# Adafruit_NeoKey_Breakout.net
KiCad netlist of a schematic drawn in EAGLE
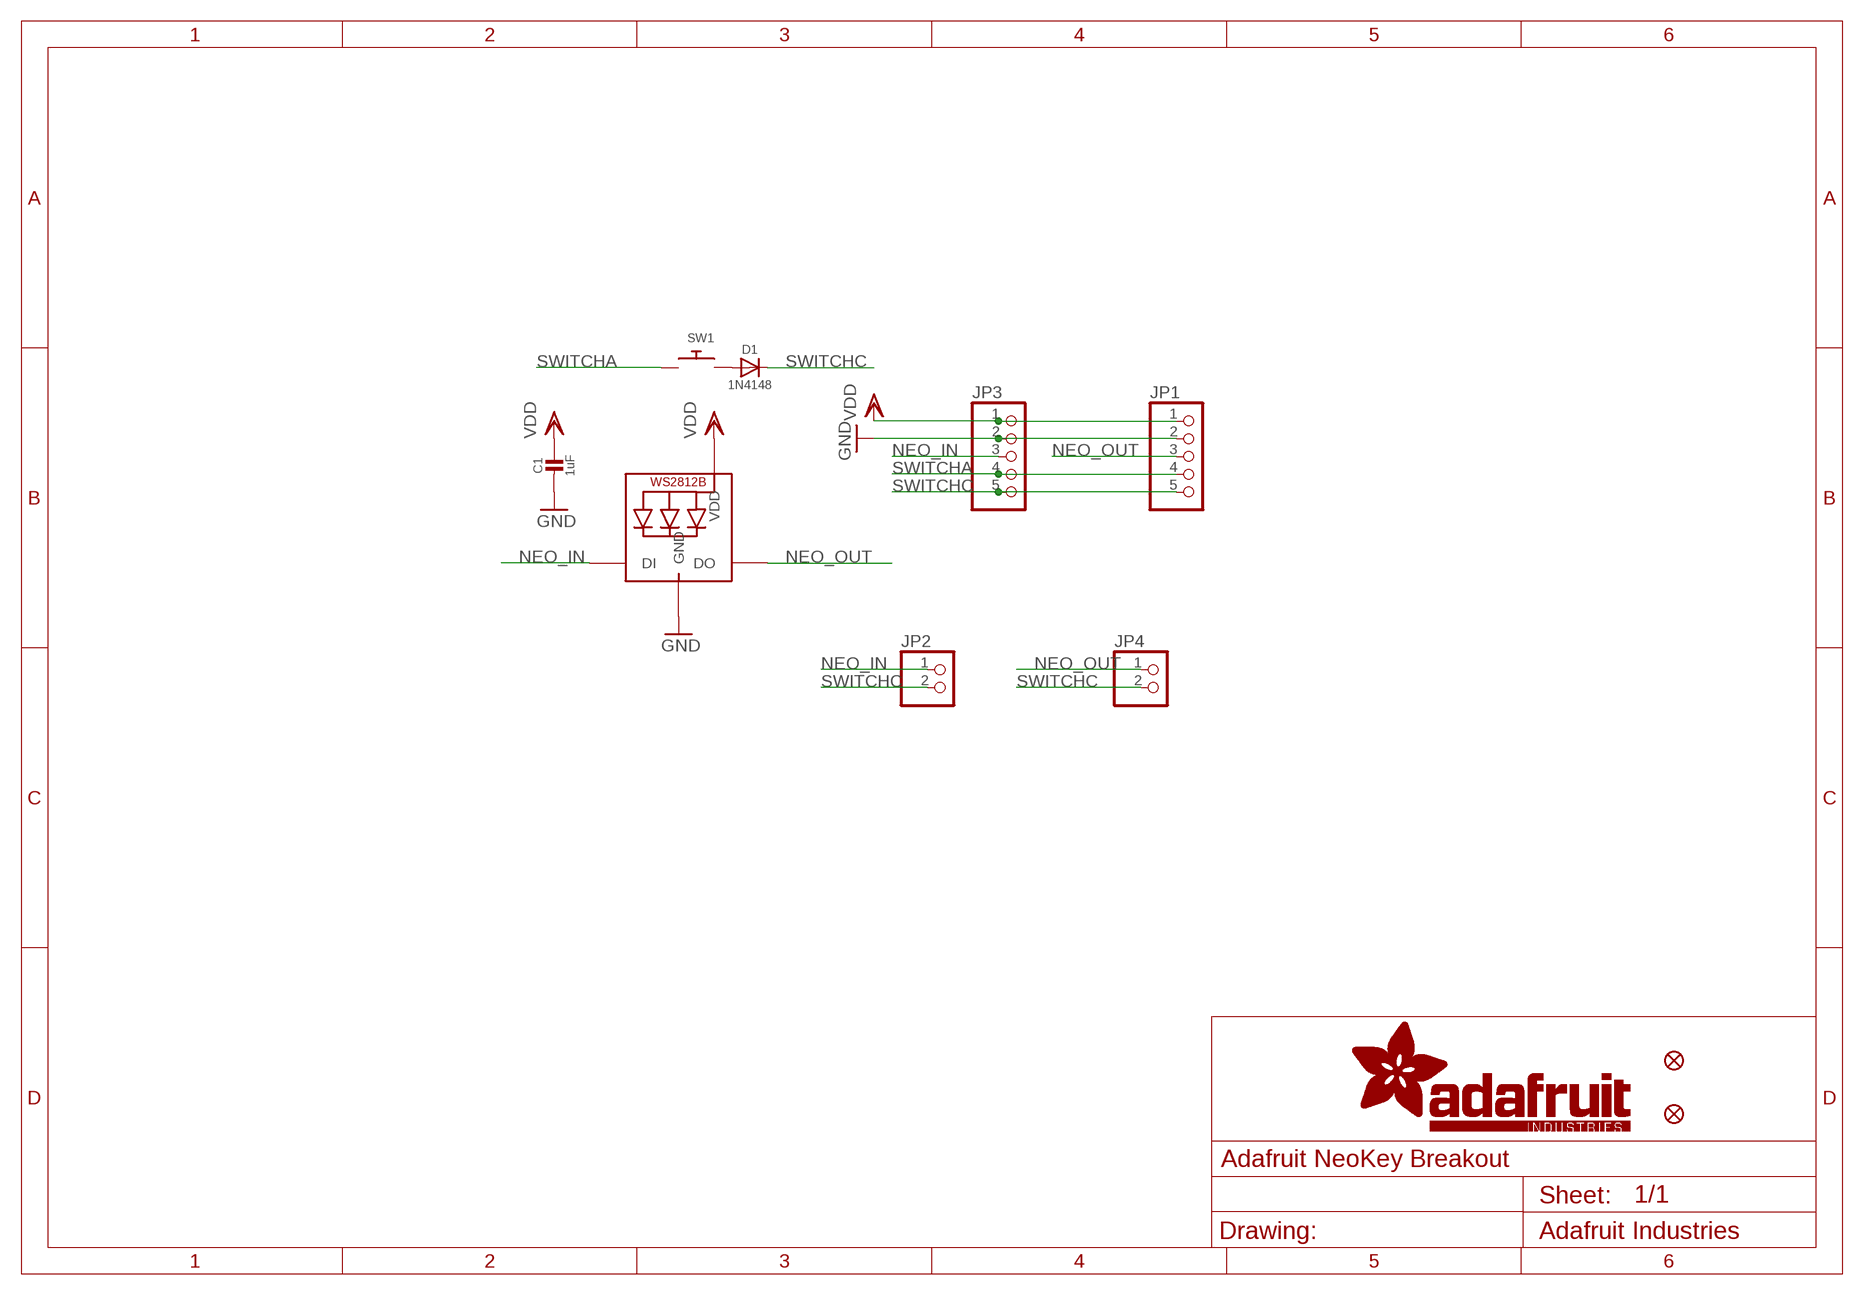
[diagram p0: schematic, sheet 1]

(export (version "E")
  (design (tool "Eeschema 10.0.6"))
  (components
    (comp (ref "C1")
      (value "1uF")
      (footprint "eagle-import:0603-NO")
      (libsource (lib "eagle-import") (part "CAP_CERAMIC0603_NO"))
    )
    (comp (ref "D1")
      (value "1N4148")
      (footprint "eagle-import:SOD-323")
      (libsource (lib "eagle-import") (part "DIODESOD-323"))
    )
    (comp (ref "FID3")
      (value "FIDUCIAL_1MM")
      (footprint "eagle-import:FIDUCIAL_1MM")
      (libsource (lib "eagle-import") (part "FIDUCIAL_1MM"))
    )
    (comp (ref "FID4")
      (value "FIDUCIAL_1MM")
      (footprint "eagle-import:FIDUCIAL_1MM")
      (libsource (lib "eagle-import") (part "FIDUCIAL_1MM"))
    )
    (comp (ref "JP1")
      (value "HEADER-1X570MIL")
      (footprint "eagle-import:1X05_ROUND_70")
      (libsource (lib "eagle-import") (part "HEADER-1X570MIL"))
    )
    (comp (ref "JP2")
      (value "HEADER-1X2ROUND")
      (footprint "eagle-import:1X02_ROUND")
      (libsource (lib "eagle-import") (part "HEADER-1X2ROUND"))
    )
    (comp (ref "JP3")
      (value "HEADER-1X570MIL")
      (footprint "eagle-import:1X05_ROUND_70")
      (libsource (lib "eagle-import") (part "HEADER-1X570MIL"))
    )
    (comp (ref "JP4")
      (value "HEADER-1X2ROUND")
      (footprint "eagle-import:1X02_ROUND")
      (libsource (lib "eagle-import") (part "HEADER-1X2ROUND"))
    )
    (comp (ref "LED1")
      (value "WS2812B_SK6812E")
      (footprint "eagle-import:NEO3535_REVERSE")
      (libsource (lib "eagle-import") (part "WS2812B_SK6812E"))
    )
    (comp (ref "SW1")
      (value "SWITCH_PUSHBUTTON_KAILH_SOCKET")
      (footprint "eagle-import:KAILH_SOCKET")
      (libsource (lib "eagle-import") (part "SWITCH_PUSHBUTTON_KAILH_SOCKET"))
    )
  )
  (nets
    (net (code "1") (name "/NEO_IN") (class "Default")
      (node (ref "JP2") (pin "1") (pinfunction "1_1") (pintype "passive"))
      (node (ref "JP3") (pin "3") (pinfunction "3_3") (pintype "passive"))
      (node (ref "LED1") (pin "4-DIN") (pinfunction "DI_4-DIN") (pintype "input"))
    )
    (net (code "2") (name "/NEO_OUT") (class "Default")
      (node (ref "JP1") (pin "3") (pinfunction "3_3") (pintype "passive"))
      (node (ref "JP4") (pin "1") (pinfunction "1_1") (pintype "passive"))
      (node (ref "LED1") (pin "2-DOUT") (pinfunction "DO_2-DOUT") (pintype "output"))
    )
    (net (code "3") (name "/SWITCHA") (class "Default")
      (node (ref "JP1") (pin "4") (pinfunction "4_4") (pintype "passive"))
      (node (ref "JP3") (pin "4") (pinfunction "4_4") (pintype "passive"))
      (node (ref "SW1") (pin "2") (pinfunction "P$2_2") (pintype "passive"))
    )
    (net (code "4") (name "/SWITCHC") (class "Default")
      (node (ref "D1") (pin "C") (pinfunction "C_C") (pintype "passive"))
      (node (ref "JP1") (pin "5") (pinfunction "5_5") (pintype "passive"))
      (node (ref "JP2") (pin "2") (pinfunction "2_2") (pintype "passive"))
      (node (ref "JP3") (pin "5") (pinfunction "5_5") (pintype "passive"))
      (node (ref "JP4") (pin "2") (pinfunction "2_2") (pintype "passive"))
    )
    (net (code "5") (name "GND") (class "Default")
      (node (ref "C1") (pin "2") (pinfunction "2_2") (pintype "passive"))
      (node (ref "JP1") (pin "2") (pinfunction "2_2") (pintype "passive"))
      (node (ref "JP3") (pin "2") (pinfunction "2_2") (pintype "passive"))
      (node (ref "LED1") (pin "3-GND") (pinfunction "GND_3-GND") (pintype "power_in"))
    )
    (net (code "6") (name "Net-(SW1-P$1)") (class "Default")
      (node (ref "D1") (pin "A") (pinfunction "A_A") (pintype "passive"))
      (node (ref "SW1") (pin "1") (pinfunction "P$1_1") (pintype "passive"))
    )
    (net (code "7") (name "VDD") (class "Default")
      (node (ref "C1") (pin "1") (pinfunction "1_1") (pintype "passive"))
      (node (ref "JP1") (pin "1") (pinfunction "1_1") (pintype "passive"))
      (node (ref "JP3") (pin "1") (pinfunction "1_1") (pintype "passive"))
      (node (ref "LED1") (pin "1-VDD") (pinfunction "VDD_1-VDD") (pintype "power_in"))
    )
  )
)
